# ProPrj_Hackclub-NFC-Card_2025-01-11.net
KiCad netlist of a schematic drawn in EasyEDA Pro
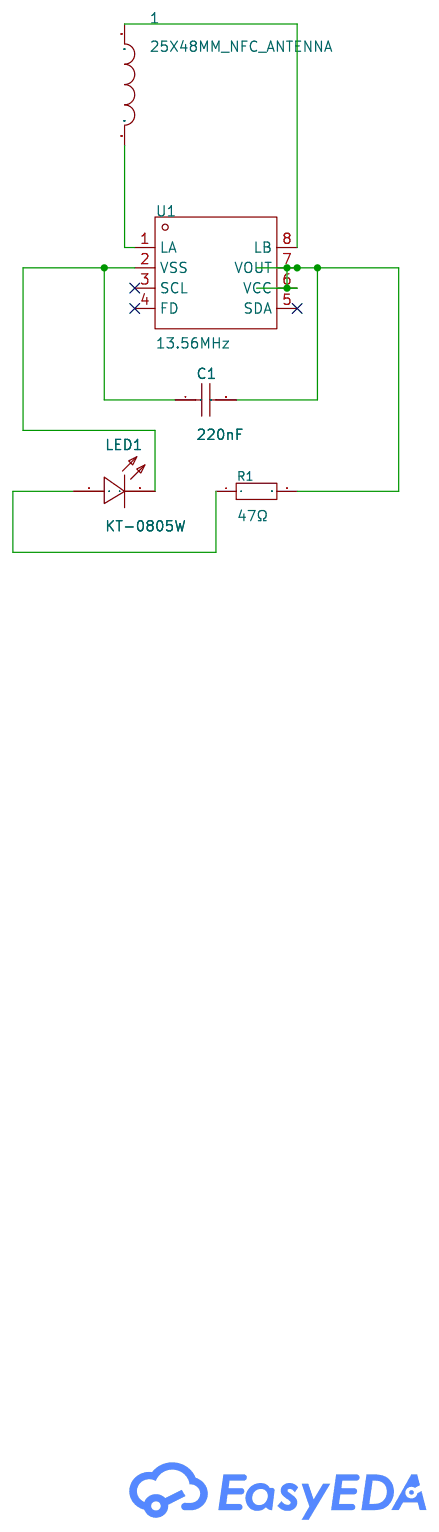
[diagram p0: schematic sheet]

(export (version "E")
  (design (tool "Eeschema 10.0.6"))
  (components
    (comp (ref "1") (value "25X48MM_NFC_ANTENNA") (libsource (lib "easyedapro") (part "25X48MM_NFC_ANTENNA")))
    (comp (ref "C1")
      (value "220nF")
      (footprint "easyedapro:C0603")
      (fields
        (field (name "Manufacturer Part") "CL10B224KA8NNNC")
        (field (name "Manufacturer") "SAMSUNG(三星)")
      )
      (libsource (lib "easyedapro") (part "CL10B224KA8NNNC"))
    )
    (comp (ref "LED1")
      (value "KT-0805W")
      (footprint "easyedapro:LED0805-R-RD")
      (fields (field (name "Manufacturer") "KENTO"))
      (libsource (lib "easyedapro") (part "whiteLEDSMD"))
    )
    (comp (ref "R1")
      (value "47Ω")
      (footprint "easyedapro:R0603")
      (fields
        (field (name "Manufacturer Part") "0603WAF470JT5E")
        (field (name "Manufacturer") "UNI-ROYAL(厚声)")
      )
      (libsource (lib "easyedapro") (part "0603WAF470JT5E"))
    )
    (comp (ref "U1")
      (value "13.56MHz")
      (footprint "easyedapro:XQFN-8_L1.6-W1.6-P0.50-BL_NT3H2111W0FHKH")
      (fields (field (name "Manufacturer Part") "NT3H2111W0FHKH") (field (name "Manufacturer") "NXP(恩智浦)"))
      (libsource (lib "easyedapro") (part "NT3H2111W0FHKH"))
    )
  )
  (nets
    (net (code "1") (name "Net-(LED1-A)") (class "Default")
      (node (ref "LED1") (pin "1") (pinfunction "A_1") (pintype "unspecified"))
      (node (ref "R1") (pin "1") (pinfunction "1_1") (pintype "input"))
    )
    (net (code "2") (name "Net-(LED1-K)") (class "Default")
      (node (ref "C1") (pin "1") (pinfunction "1_1") (pintype "input"))
      (node (ref "LED1") (pin "2") (pinfunction "K_2") (pintype "unspecified"))
      (node (ref "U1") (pin "2") (pinfunction "VSS_2") (pintype "unspecified"))
    )
    (net (code "3") (name "Net-(U1-LA)") (class "Default")
      (node (ref "1") (pin "P$2") (pinfunction "P$2_P$2") (pintype "bidirectional"))
      (node (ref "U1") (pin "1") (pinfunction "LA_1") (pintype "unspecified"))
    )
    (net (code "4") (name "Net-(U1-LB)") (class "Default")
      (node (ref "1") (pin "P$1") (pinfunction "P$1_P$1") (pintype "bidirectional"))
      (node (ref "U1") (pin "8") (pinfunction "LB_8") (pintype "unspecified"))
    )
    (net (code "5") (name "Net-(U1-VCC)") (class "Default")
      (node (ref "C1") (pin "2") (pinfunction "2_2") (pintype "input"))
      (node (ref "R1") (pin "2") (pinfunction "2_2") (pintype "input"))
      (node (ref "U1") (pin "6") (pinfunction "VCC_6") (pintype "unspecified"))
      (node (ref "U1") (pin "7") (pinfunction "VOUT_7") (pintype "unspecified"))
    )
    (net (code "6") (name "unconnected-(U1-FD-Pad4)") (class "Default")
      (node (ref "U1") (pin "4") (pinfunction "FD_4") (pintype "unspecified+no_connect"))
    )
    (net (code "7") (name "unconnected-(U1-SCL-Pad3)") (class "Default")
      (node (ref "U1") (pin "3") (pinfunction "SCL_3") (pintype "unspecified+no_connect"))
    )
    (net (code "8") (name "unconnected-(U1-SDA-Pad5)") (class "Default")
      (node (ref "U1") (pin "5") (pinfunction "SDA_5") (pintype "unspecified+no_connect"))
    )
  )
)
